# 03_SOC_PORT0_2.net
KiCad netlist of a schematic drawn in Altium Designer
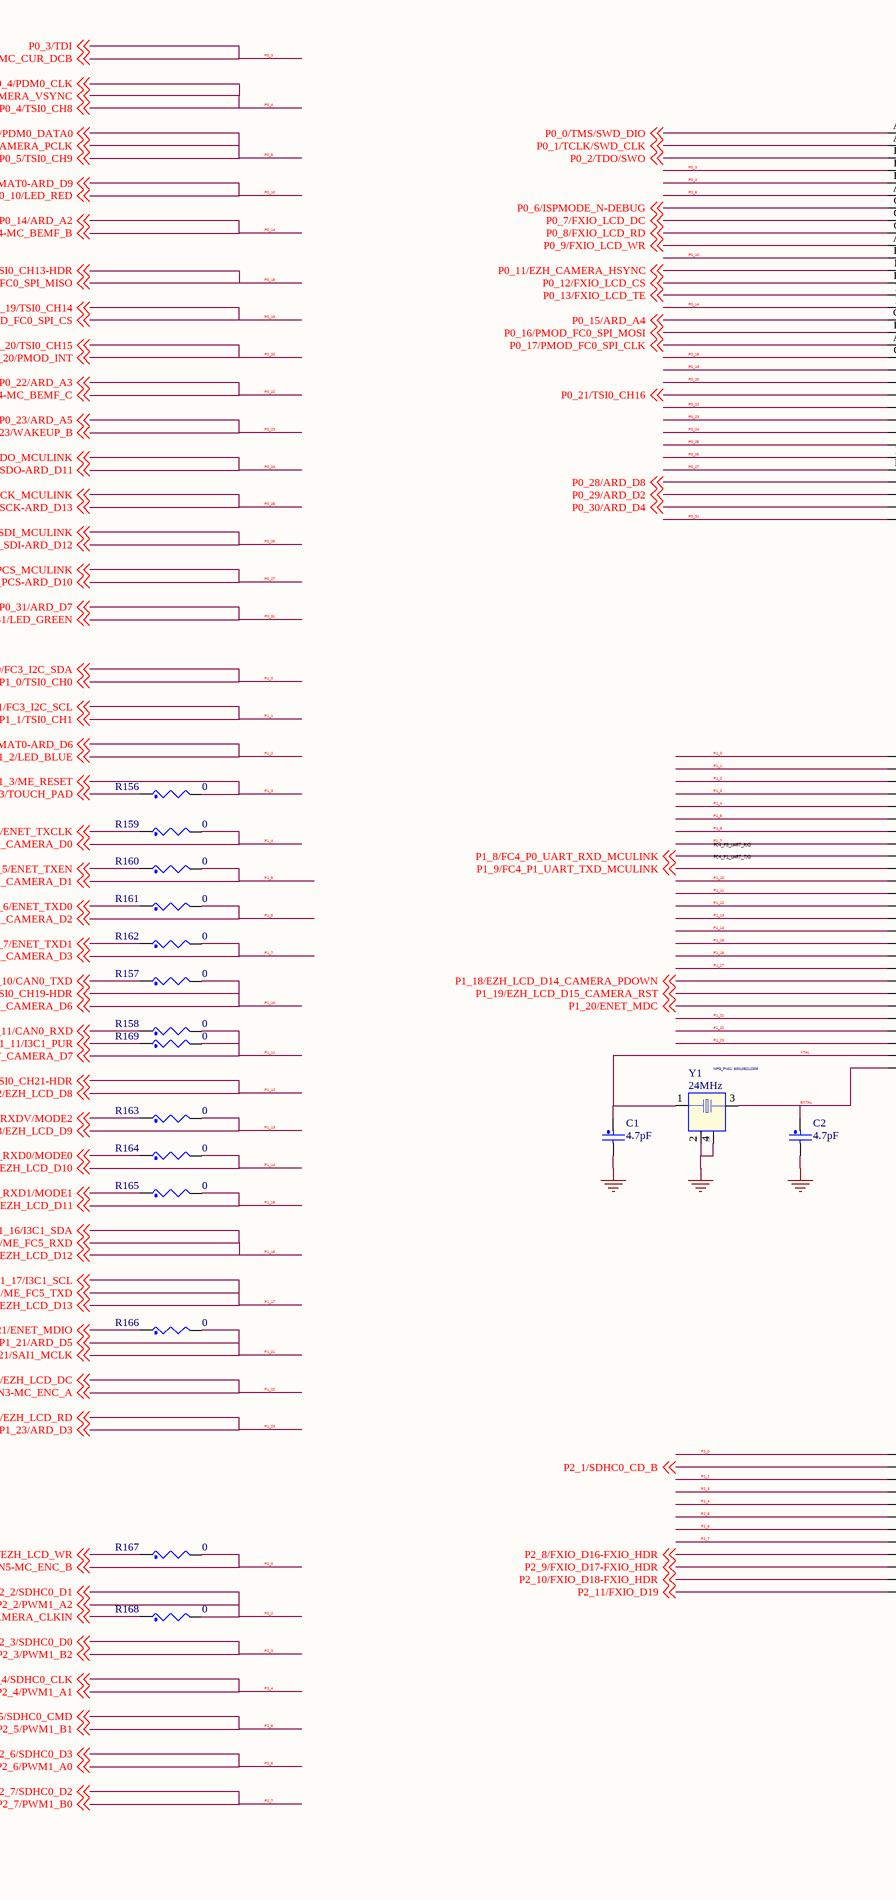
[diagram p0: 03 SOC_PORT0~2.SchDoc, left]
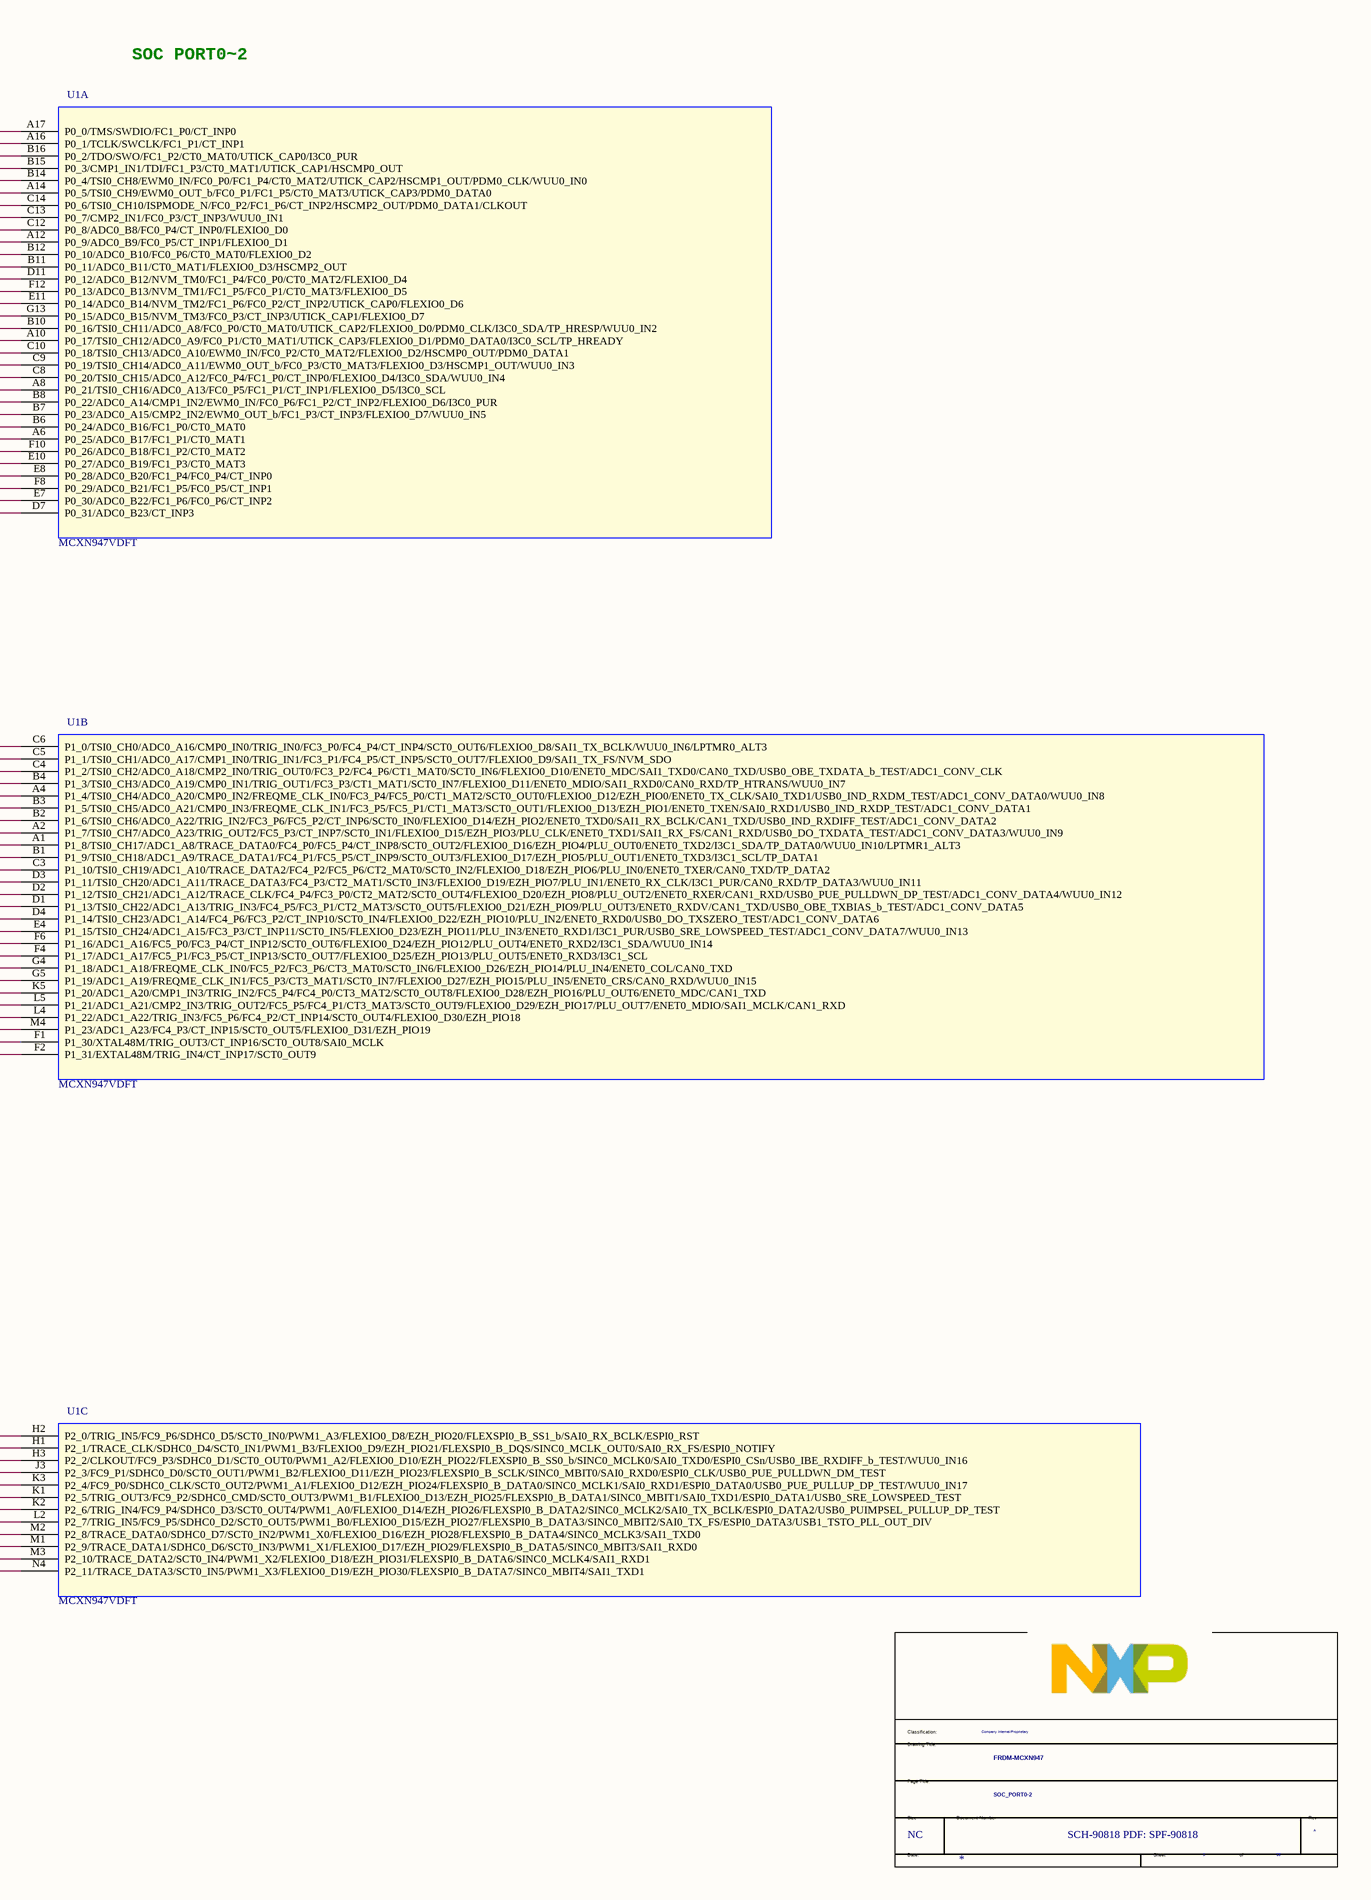
[diagram p1: 03 SOC_PORT0~2.SchDoc, right]

(export (version "E")
  (design (tool "Eeschema 10.0.6"))
  (components
    (comp (ref "C1")
      (value "4.7pF")
      (footprint "CC0402_25")
      (description "CAP CER 4.7PF 50V 0.5pF C0G 0402")
      (fields (field (name "TOLERANCE") "0.5pF"))
      (libsource (lib "*") (part "CAP_NP"))
    )
    (comp (ref "C2")
      (value "4.7pF")
      (footprint "CC0402_25")
      (description "CAP CER 4.7PF 50V 0.5pF C0G 0402")
      (fields (field (name "TOLERANCE") "0.5pF"))
      (libsource (lib "*") (part "CAP_NP"))
    )
    (comp (ref "R156")
      (value "0")
      (footprint "RC0603_OV")
      (description "RES MF ZERO OHM 1/10W -- 0603")
      (libsource (lib "*") (part "RES"))
    )
    (comp (ref "R157")
      (value "0")
      (footprint "RC0603_OV")
      (description "RES MF ZERO OHM 1/10W -- 0603")
      (libsource (lib "*") (part "RES"))
    )
    (comp (ref "R158")
      (value "0")
      (footprint "RC0603_OV")
      (description "RES MF ZERO OHM 1/10W -- 0603")
      (libsource (lib "*") (part "RES"))
    )
    (comp (ref "R159")
      (value "0")
      (footprint "RC0603_OV")
      (description "RES MF ZERO OHM 1/10W -- 0603")
      (libsource (lib "*") (part "RES"))
    )
    (comp (ref "R160")
      (value "0")
      (footprint "RC0603_OV")
      (description "RES MF ZERO OHM 1/10W -- 0603")
      (libsource (lib "*") (part "RES"))
    )
    (comp (ref "R161")
      (value "0")
      (footprint "RC0603_OV")
      (description "RES MF ZERO OHM 1/10W -- 0603")
      (libsource (lib "*") (part "RES"))
    )
    (comp (ref "R162")
      (value "0")
      (footprint "RC0603_OV")
      (description "RES MF ZERO OHM 1/10W -- 0603")
      (libsource (lib "*") (part "RES"))
    )
    (comp (ref "R163")
      (value "0")
      (footprint "RC0603_OV")
      (description "RES MF ZERO OHM 1/10W -- 0603")
      (libsource (lib "*") (part "RES"))
    )
    (comp (ref "R164")
      (value "0")
      (footprint "RC0603_OV")
      (description "RES MF ZERO OHM 1/10W -- 0603")
      (libsource (lib "*") (part "RES"))
    )
    (comp (ref "R165")
      (value "0")
      (footprint "RC0603_OV")
      (description "RES MF ZERO OHM 1/10W -- 0603")
      (libsource (lib "*") (part "RES"))
    )
    (comp (ref "R166")
      (value "0")
      (footprint "RC0603_OV")
      (description "RES MF ZERO OHM 1/10W -- 0603")
      (libsource (lib "*") (part "RES"))
    )
    (comp (ref "R167")
      (value "0")
      (footprint "RC0402_25")
      (description "RES MF ZERO OHM 1/16W 5% 0402")
      (fields (field (name "TOLERANCE") "5%"))
      (libsource (lib "*") (part "RES"))
    )
    (comp (ref "R168")
      (value "0")
      (footprint "RC0603_OV")
      (description "RES MF ZERO OHM 1/10W -- 0603")
      (libsource (lib "*") (part "RES"))
    )
    (comp (ref "R169")
      (value "0")
      (footprint "RC0402_25")
      (description "RES MF ZERO OHM 1/16W 5% 0402")
      (fields (field (name "TOLERANCE") "5%"))
      (libsource (lib "*") (part "RES"))
    )
    (comp (ref "U1")
      (value "MCXN947VDFT")
      (footprint "bga184_0p5_9x9_sm")
      (description "IC MCU LOW POWER 150MHz ARM Nirvana -- VFBGA184")
      (libsource (lib "*") (part "MCXN947VDFT_BGA_184P"))
    )
    (comp (ref "Y1")
      (value "24MHz")
      (footprint "xtal4_2p1x1p7mm_sm")
      (description "XTAL 24MHz 10ppm 8pF SMT")
      (fields (field (name "MFG_PN01") "830108212309"))
      (libsource (lib "*") (part "XTAL_4PIN"))
    )
  )
  (nets
    (net (code "1") (name "/EXTAL") (class "Default")
      (node (ref "C2") (pin "1") (pinfunction "1_1") (pintype "passive"))
      (node (ref "U1") (pin "F2") (pinfunction "P1_31/EXTAL48M/TRIG_IN4/CT_INP17/SCT0_OUT9_F2") (pintype "passive"))
      (node (ref "Y1") (pin "3") (pinfunction "3_3") (pintype "passive"))
    )
    (net (code "2") (name "/XTAL") (class "Default")
      (node (ref "C1") (pin "1") (pinfunction "1_1") (pintype "passive"))
      (node (ref "U1") (pin "F1") (pinfunction "P1_30/XTAL48M/TRIG_OUT3/CT_INP16/SCT0_OUT8/SAI0_MCLK_F1") (pintype "passive"))
      (node (ref "Y1") (pin "1") (pinfunction "1_1") (pintype "passive"))
    )
    (net (code "3") (name "GND") (class "Default")
      (node (ref "C1") (pin "2") (pinfunction "2_2") (pintype "passive"))
      (node (ref "C2") (pin "2") (pinfunction "2_2") (pintype "passive"))
      (node (ref "Y1") (pin "2") (pinfunction "GND1_2") (pintype "power_in"))
      (node (ref "Y1") (pin "4") (pinfunction "GND2_4") (pintype "power_in"))
    )
    (net (code "4") (name "P0_0{slash}TMS{slash}SWD_DIO") (class "Default")
      (node (ref "U1") (pin "A17") (pinfunction "P0_0/TMS/SWDIO/FC1_P0/CT_INP0_A17") (pintype "passive"))
    )
    (net (code "5") (name "P0_1{slash}TCLK{slash}SWD_CLK") (class "Default")
      (node (ref "U1") (pin "A16") (pinfunction "P0_1/TCLK/SWCLK/FC1_P1/CT_INP1_A16") (pintype "passive"))
    )
    (net (code "6") (name "P0_2{slash}TDO{slash}SWO") (class "Default")
      (node (ref "U1") (pin "B16") (pinfunction "P0_2/TDO/SWO/FC1_P2/CT0_MAT0/UTICK_CAP0/I3C0_PUR_B16") (pintype "passive"))
    )
    (net (code "7") (name "P0_3{slash}CMP1_IN1-MC_CUR_DCB") (class "Default")
      (node (ref "U1") (pin "B15") (pinfunction "P0_3/CMP1_IN1/TDI/FC1_P3/CT0_MAT1/UTICK_CAP1/HSCMP0_OUT_B15") (pintype "passive"))
    )
    (net (code "8") (name "P0_4{slash}EZH_CAMERA_VSYNC") (class "Default")
      (node (ref "U1") (pin "B14") (pinfunction "P0_4/TSI0_CH8/EWM0_IN/FC0_P0/FC1_P4/CT0_MAT2/UTICK_CAP2/HSCMP1_OUT/PDM0_CLK/WUU0_IN0_B14") (pintype "passive"))
    )
    (net (code "9") (name "P0_5{slash}EZH_CAMERA_PCLK") (class "Default")
      (node (ref "U1") (pin "A14") (pinfunction "P0_5/TSI0_CH9/EWM0_OUT_b/FC0_P1/FC1_P5/CT0_MAT3/UTICK_CAP3/PDM0_DATA0_A14") (pintype "passive"))
    )
    (net (code "10") (name "P0_6{slash}ISPMODE_N-DEBUG") (class "Default")
      (node (ref "U1") (pin "C14") (pinfunction "P0_6/TSI0_CH10/ISPMODE_N/FC0_P2/FC1_P6/CT_INP2/HSCMP2_OUT/PDM0_DATA1/CLKOUT_C14") (pintype "passive"))
    )
    (net (code "11") (name "P0_7{slash}FXIO_LCD_DC") (class "Default")
      (node (ref "U1") (pin "C13") (pinfunction "P0_7/CMP2_IN1/FC0_P3/CT_INP3/WUU0_IN1_C13") (pintype "passive"))
    )
    (net (code "12") (name "P0_8{slash}FXIO_LCD_RD") (class "Default")
      (node (ref "U1") (pin "C12") (pinfunction "P0_8/ADC0_B8/FC0_P4/CT_INP0/FLEXIO0_D0_C12") (pintype "passive"))
    )
    (net (code "13") (name "P0_9{slash}FXIO_LCD_WR") (class "Default")
      (node (ref "U1") (pin "A12") (pinfunction "P0_9/ADC0_B9/FC0_P5/CT_INP1/FLEXIO0_D1_A12") (pintype "passive"))
    )
    (net (code "14") (name "P0_10{slash}CT0_MAT0-ARD_D9") (class "Default")
      (node (ref "U1") (pin "B12") (pinfunction "P0_10/ADC0_B10/FC0_P6/CT0_MAT0/FLEXIO0_D2_B12") (pintype "passive"))
    )
    (net (code "15") (name "P0_11{slash}EZH_CAMERA_HSYNC") (class "Default")
      (node (ref "U1") (pin "B11") (pinfunction "P0_11/ADC0_B11/CT0_MAT1/FLEXIO0_D3/HSCMP2_OUT_B11") (pintype "passive"))
    )
    (net (code "16") (name "P0_12{slash}FXIO_LCD_CS") (class "Default")
      (node (ref "U1") (pin "D11") (pinfunction "P0_12/ADC0_B12/NVM_TM0/FC1_P4/FC0_P0/CT0_MAT2/FLEXIO0_D4_D11") (pintype "passive"))
    )
    (net (code "17") (name "P0_13{slash}FXIO_LCD_TE") (class "Default")
      (node (ref "U1") (pin "F12") (pinfunction "P0_13/ADC0_B13/NVM_TM1/FC1_P5/FC0_P1/CT0_MAT3/FLEXIO0_D5_F12") (pintype "passive"))
    )
    (net (code "18") (name "P0_14{slash}ADC0_B14-MC_BEMF_B") (class "Default")
      (node (ref "U1") (pin "E11") (pinfunction "P0_14/ADC0_B14/NVM_TM2/FC1_P6/FC0_P2/CT_INP2/UTICK_CAP0/FLEXIO0_D6_E11") (pintype "passive"))
    )
    (net (code "19") (name "P0_15{slash}ARD_A4") (class "Default")
      (node (ref "U1") (pin "G13") (pinfunction "P0_15/ADC0_B15/NVM_TM3/FC0_P3/CT_INP3/UTICK_CAP1/FLEXIO0_D7_G13") (pintype "passive"))
    )
    (net (code "20") (name "P0_16{slash}PMOD_FC0_SPI_MOSI") (class "Default")
      (node (ref "U1") (pin "B10") (pinfunction "P0_16/TSI0_CH11/ADC0_A8/FC0_P0/CT0_MAT0/UTICK_CAP2/FLEXIO0_D0/PDM0_CLK/I3C0_SDA/TP_HRESP/WUU0_IN2_B10") (pintype "passive"))
    )
    (net (code "21") (name "P0_17{slash}PMOD_FC0_SPI_CLK") (class "Default")
      (node (ref "U1") (pin "A10") (pinfunction "P0_17/TSI0_CH12/ADC0_A9/FC0_P1/CT0_MAT1/UTICK_CAP3/FLEXIO0_D1/PDM0_DATA0/I3C0_SCL/TP_HREADY_A10") (pintype "passive"))
    )
    (net (code "22") (name "P0_18{slash}PMOD_FC0_SPI_MISO") (class "Default")
      (node (ref "U1") (pin "C10") (pinfunction "P0_18/TSI0_CH13/ADC0_A10/EWM0_IN/FC0_P2/CT0_MAT2/FLEXIO0_D2/HSCMP0_OUT/PDM0_DATA1_C10") (pintype "passive"))
    )
    (net (code "23") (name "P0_19{slash}PMOD_FC0_SPI_CS") (class "Default")
      (node (ref "U1") (pin "C9") (pinfunction "P0_19/TSI0_CH14/ADC0_A11/EWM0_OUT_b/FC0_P3/CT0_MAT3/FLEXIO0_D3/HSCMP1_OUT/WUU0_IN3_C9") (pintype "passive"))
    )
    (net (code "24") (name "P0_20{slash}PMOD_INT") (class "Default")
      (node (ref "U1") (pin "C8") (pinfunction "P0_20/TSI0_CH15/ADC0_A12/FC0_P4/FC1_P0/CT_INP0/FLEXIO0_D4/I3C0_SDA/WUU0_IN4_C8") (pintype "passive"))
    )
    (net (code "25") (name "P0_21{slash}TSI0_CH16") (class "Default")
      (node (ref "U1") (pin "A8") (pinfunction "P0_21/TSI0_CH16/ADC0_A13/FC0_P5/FC1_P1/CT_INP1/FLEXIO0_D5/I3C0_SCL_A8") (pintype "passive"))
    )
    (net (code "26") (name "P0_22{slash}ADC0_A14-MC_BEMF_C") (class "Default")
      (node (ref "U1") (pin "B8") (pinfunction "P0_22/ADC0_A14/CMP1_IN2/EWM0_IN/FC0_P6/FC1_P2/CT_INP2/FLEXIO0_D6/I3C0_PUR_B8") (pintype "passive"))
    )
    (net (code "27") (name "P0_23{slash}ARD_A5") (class "Default")
      (node (ref "U1") (pin "B7") (pinfunction "P0_23/ADC0_A15/CMP2_IN2/EWM0_OUT_b/FC1_P3/CT_INP3/FLEXIO0_D7/WUU0_IN5_B7") (pintype "passive"))
    )
    (net (code "28") (name "P0_24{slash}FC1_SPI_SDO-ARD_D11") (class "Default")
      (node (ref "U1") (pin "B6") (pinfunction "P0_24/ADC0_B16/FC1_P0/CT0_MAT0_B6") (pintype "passive"))
    )
    (net (code "29") (name "P0_25{slash}FCI_SPI_SCK-ARD_D13") (class "Default")
      (node (ref "U1") (pin "A6") (pinfunction "P0_25/ADC0_B17/FC1_P1/CT0_MAT1_A6") (pintype "passive"))
    )
    (net (code "30") (name "P0_26{slash}FC1_SPI_SDI-ARD_D12") (class "Default")
      (node (ref "U1") (pin "F10") (pinfunction "P0_26/ADC0_B18/FC1_P2/CT0_MAT2_F10") (pintype "passive"))
    )
    (net (code "31") (name "P0_27{slash}FC1_SPI_PCS-ARD_D10") (class "Default")
      (node (ref "U1") (pin "E10") (pinfunction "P0_27/ADC0_B19/FC1_P3/CT0_MAT3_E10") (pintype "passive"))
    )
    (net (code "32") (name "P0_28{slash}ARD_D8") (class "Default")
      (node (ref "U1") (pin "E8") (pinfunction "P0_28/ADC0_B20/FC1_P4/FC0_P4/CT_INP0_E8") (pintype "passive"))
    )
    (net (code "33") (name "P0_29{slash}ARD_D2") (class "Default")
      (node (ref "U1") (pin "F8") (pinfunction "P0_29/ADC0_B21/FC1_P5/FC0_P5/CT_INP1_F8") (pintype "passive"))
    )
    (net (code "34") (name "P0_30{slash}ARD_D4") (class "Default")
      (node (ref "U1") (pin "E7") (pinfunction "P0_30/ADC0_B22/FC1_P6/FC0_P6/CT_INP2_E7") (pintype "passive"))
    )
    (net (code "35") (name "P0_31{slash}ARD_D7") (class "Default")
      (node (ref "U1") (pin "D7") (pinfunction "P0_31/ADC0_B23/CT_INP3_D7") (pintype "passive"))
    )
    (net (code "36") (name "P1_0{slash}FC3_I2C_SDA") (class "Default")
      (node (ref "U1") (pin "C6") (pinfunction "P1_0/TSI0_CH0/ADC0_A16/CMP0_IN0/TRIG_IN0/FC3_P0/FC4_P4/CT_INP4/SCT0_OUT6/FLEXIO0_D8/SAI1_TX_BCLK/WUU0_IN6/LPTMR0_ALT3_C6") (pintype "passive"))
    )
    (net (code "37") (name "P1_1{slash}FC3_I2C_SCL") (class "Default")
      (node (ref "U1") (pin "C5") (pinfunction "P1_1/TSI0_CH1/ADC0_A17/CMP1_IN0/TRIG_IN1/FC3_P1/FC4_P5/CT_INP5/SCT0_OUT7/FLEXIO0_D9/SAI1_TX_FS/NVM_SDO_C5") (pintype "passive"))
    )
    (net (code "38") (name "P1_2{slash}CT1_MAT0-ARD_D6") (class "Default")
      (node (ref "U1") (pin "C4") (pinfunction "P1_2/TSI0_CH2/ADC0_A18/CMP2_IN0/TRIG_OUT0/FC3_P2/FC4_P6/CT1_MAT0/SCT0_IN6/FLEXIO0_D10/ENET0_MDC/SAI1_TXD0/CAN0_TXD/USB0_OBE_TXDATA_b_TEST/ADC1_CONV_CLK_C4") (pintype "passive"))
    )
    (net (code "39") (name "P1_3{slash}ME_RESET") (class "Default")
      (node (ref "R156") (pin "2") (pinfunction "2_2") (pintype "passive"))
      (node (ref "U1") (pin "B4") (pinfunction "P1_3/TSI0_CH3/ADC0_A19/CMP0_IN1/TRIG_OUT1/FC3_P3/CT1_MAT1/SCT0_IN7/FLEXIO0_D11/ENET0_MDIO/SAI1_RXD0/CAN0_RXD/TP_HTRANS/WUU0_IN7_B4") (pintype "passive"))
    )
    (net (code "40") (name "P1_3{slash}TOUCH_PAD") (class "Default")
      (node (ref "R156") (pin "1") (pinfunction "1_1") (pintype "passive"))
    )
    (net (code "41") (name "P1_4{slash}ENET_TXCLK") (class "Default")
      (node (ref "R159") (pin "1") (pinfunction "1_1") (pintype "passive"))
    )
    (net (code "42") (name "P1_4{slash}EZH_LCD_D0_CAMERA_D0") (class "Default")
      (node (ref "R159") (pin "2") (pinfunction "2_2") (pintype "passive"))
      (node (ref "U1") (pin "A4") (pinfunction "P1_4/TSI0_CH4/ADC0_A20/CMP0_IN2/FREQME_CLK_IN0/FC3_P4/FC5_P0/CT1_MAT2/SCT0_OUT0/FLEXIO0_D12/EZH_PIO0/ENET0_TX_CLK/SAI0_TXD1/USB0_IND_RXDM_TEST/ADC1_CONV_DATA0/WUU0_IN8_A4") (pintype "passive"))
    )
    (net (code "43") (name "P1_5{slash}ENET_TXEN") (class "Default")
      (node (ref "R160") (pin "1") (pinfunction "1_1") (pintype "passive"))
    )
    (net (code "44") (name "P1_5{slash}EZH_LCD_D1_CAMERA_D1") (class "Default")
      (node (ref "R160") (pin "2") (pinfunction "2_2") (pintype "passive"))
      (node (ref "U1") (pin "B3") (pinfunction "P1_5/TSI0_CH5/ADC0_A21/CMP0_IN3/FREQME_CLK_IN1/FC3_P5/FC5_P1/CT1_MAT3/SCT0_OUT1/FLEXIO0_D13/EZH_PIO1/ENET0_TXEN/SAI0_RXD1/USB0_IND_RXDP_TEST/ADC1_CONV_DATA1_B3") (pintype "passive"))
    )
    (net (code "45") (name "P1_6{slash}ENET_TXD0") (class "Default")
      (node (ref "R161") (pin "1") (pinfunction "1_1") (pintype "passive"))
    )
    (net (code "46") (name "P1_6{slash}EZH_LCD_D2_CAMERA_D2") (class "Default")
      (node (ref "R161") (pin "2") (pinfunction "2_2") (pintype "passive"))
      (node (ref "U1") (pin "B2") (pinfunction "P1_6/TSI0_CH6/ADC0_A22/TRIG_IN2/FC3_P6/FC5_P2/CT_INP6/SCT0_IN0/FLEXIO0_D14/EZH_PIO2/ENET0_TXD0/SAI1_RX_BCLK/CAN1_TXD/USB0_IND_RXDIFF_TEST/ADC1_CONV_DATA2_B2") (pintype "passive"))
    )
    (net (code "47") (name "P1_7{slash}ENET_TXD1") (class "Default")
      (node (ref "R162") (pin "1") (pinfunction "1_1") (pintype "passive"))
    )
    (net (code "48") (name "P1_7{slash}EZH_LCD_D3_CAMERA_D3") (class "Default")
      (node (ref "R162") (pin "2") (pinfunction "2_2") (pintype "passive"))
      (node (ref "U1") (pin "A2") (pinfunction "P1_7/TSI0_CH7/ADC0_A23/TRIG_OUT2/FC5_P3/CT_INP7/SCT0_IN1/FLEXIO0_D15/EZH_PIO3/PLU_CLK/ENET0_TXD1/SAI1_RX_FS/CAN1_RXD/USB0_DO_TXDATA_TEST/ADC1_CONV_DATA3/WUU0_IN9_A2") (pintype "passive"))
    )
    (net (code "49") (name "P1_8{slash}FC4_P0_UART_RXD_MCULINK") (class "Default")
      (node (ref "U1") (pin "A1") (pinfunction "P1_8/TSI0_CH17/ADC1_A8/TRACE_DATA0/FC4_P0/FC5_P4/CT_INP8/SCT0_OUT2/FLEXIO0_D16/EZH_PIO4/PLU_OUT0/ENET0_TXD2/I3C1_SDA/TP_DATA0/WUU0_IN10/LPTMR1_ALT3_A1") (pintype "passive"))
    )
    (net (code "50") (name "P1_9{slash}FC4_P1_UART_TXD_MCULINK") (class "Default")
      (node (ref "U1") (pin "B1") (pinfunction "P1_9/TSI0_CH18/ADC1_A9/TRACE_DATA1/FC4_P1/FC5_P5/CT_INP9/SCT0_OUT3/FLEXIO0_D17/EZH_PIO5/PLU_OUT1/ENET0_TXD3/I3C1_SCL/TP_DATA1_B1") (pintype "passive"))
    )
    (net (code "51") (name "P1_10{slash}CAN0_TXD") (class "Default")
      (node (ref "R157") (pin "1") (pinfunction "1_1") (pintype "passive"))
    )
    (net (code "52") (name "P1_10{slash}EZH_LCD_D6_CAMERA_D6") (class "Default")
      (node (ref "R157") (pin "2") (pinfunction "2_2") (pintype "passive"))
      (node (ref "U1") (pin "C3") (pinfunction "P1_10/TSI0_CH19/ADC1_A10/TRACE_DATA2/FC4_P2/FC5_P6/CT2_MAT0/SCT0_IN2/FLEXIO0_D18/EZH_PIO6/PLU_IN0/ENET0_TXER/CAN0_TXD/TP_DATA2_C3") (pintype "passive"))
    )
    (net (code "53") (name "P1_11{slash}CAN0_RXD") (class "Default")
      (node (ref "R158") (pin "1") (pinfunction "1_1") (pintype "passive"))
    )
    (net (code "54") (name "P1_11{slash}EZH_LCD_D7_CAMERA_D7") (class "Default")
      (node (ref "R158") (pin "2") (pinfunction "2_2") (pintype "passive"))
      (node (ref "R169") (pin "2") (pinfunction "2_2") (pintype "passive"))
      (node (ref "U1") (pin "D3") (pinfunction "P1_11/TSI0_CH20/ADC1_A11/TRACE_DATA3/FC4_P3/CT2_MAT1/SCT0_IN3/FLEXIO0_D19/EZH_PIO7/PLU_IN1/ENET0_RX_CLK/I3C1_PUR/CAN0_RXD/TP_DATA3/WUU0_IN11_D3") (pintype "passive"))
    )
    (net (code "55") (name "P1_11{slash}I3C1_PUR") (class "Default")
      (node (ref "R169") (pin "1") (pinfunction "1_1") (pintype "passive"))
    )
    (net (code "56") (name "P1_12{slash}EZH_LCD_D8") (class "Default")
      (node (ref "U1") (pin "D2") (pinfunction "P1_12/TSI0_CH21/ADC1_A12/TRACE_CLK/FC4_P4/FC3_P0/CT2_MAT2/SCT0_OUT4/FLEXIO0_D20/EZH_PIO8/PLU_OUT2/ENET0_RXER/CAN1_RXD/USB0_PUE_PULLDWN_DP_TEST/ADC1_CONV_DATA4/WUU0_IN12_D2") (pintype "passive"))
    )
    (net (code "57") (name "P1_13{slash}ENET_RXDV{slash}MODE2") (class "Default")
      (node (ref "R163") (pin "1") (pinfunction "1_1") (pintype "passive"))
    )
    (net (code "58") (name "P1_13{slash}EZH_LCD_D9") (class "Default")
      (node (ref "R163") (pin "2") (pinfunction "2_2") (pintype "passive"))
      (node (ref "U1") (pin "D1") (pinfunction "P1_13/TSI0_CH22/ADC1_A13/TRIG_IN3/FC4_P5/FC3_P1/CT2_MAT3/SCT0_OUT5/FLEXIO0_D21/EZH_PIO9/PLU_OUT3/ENET0_RXDV/CAN1_TXD/USB0_OBE_TXBIAS_b_TEST/ADC1_CONV_DATA5_D1") (pintype "passive"))
    )
    (net (code "59") (name "P1_14{slash}ENET_RXD0{slash}MODE0") (class "Default")
      (node (ref "R164") (pin "1") (pinfunction "1_1") (pintype "passive"))
    )
    (net (code "60") (name "P1_14{slash}EZH_LCD_D10") (class "Default")
      (node (ref "R164") (pin "2") (pinfunction "2_2") (pintype "passive"))
      (node (ref "U1") (pin "D4") (pinfunction "P1_14/TSI0_CH23/ADC1_A14/FC4_P6/FC3_P2/CT_INP10/SCT0_IN4/FLEXIO0_D22/EZH_PIO10/PLU_IN2/ENET0_RXD0/USB0_DO_TXSZERO_TEST/ADC1_CONV_DATA6_D4") (pintype "passive"))
    )
    (net (code "61") (name "P1_15{slash}ENET_RXD1{slash}MODE1") (class "Default")
      (node (ref "R165") (pin "1") (pinfunction "1_1") (pintype "passive"))
    )
    (net (code "62") (name "P1_15{slash}EZH_LCD_D11") (class "Default")
      (node (ref "R165") (pin "2") (pinfunction "2_2") (pintype "passive"))
      (node (ref "U1") (pin "E4") (pinfunction "P1_15/TSI0_CH24/ADC1_A15/FC3_P3/CT_INP11/SCT0_IN5/FLEXIO0_D23/EZH_PIO11/PLU_IN3/ENET0_RXD1/I3C1_PUR/USB0_SRE_LOWSPEED_TEST/ADC1_CONV_DATA7/WUU0_IN13_E4") (pintype "passive"))
    )
    (net (code "63") (name "P1_16{slash}EZH_LCD_D12") (class "Default")
      (node (ref "U1") (pin "F6") (pinfunction "P1_16/ADC1_A16/FC5_P0/FC3_P4/CT_INP12/SCT0_OUT6/FLEXIO0_D24/EZH_PIO12/PLU_OUT4/ENET0_RXD2/I3C1_SDA/WUU0_IN14_F6") (pintype "passive"))
    )
    (net (code "64") (name "P1_17{slash}EZH_LCD_D13") (class "Default")
      (node (ref "U1") (pin "F4") (pinfunction "P1_17/ADC1_A17/FC5_P1/FC3_P5/CT_INP13/SCT0_OUT7/FLEXIO0_D25/EZH_PIO13/PLU_OUT5/ENET0_RXD3/I3C1_SCL_F4") (pintype "passive"))
    )
    (net (code "65") (name "P1_18{slash}EZH_LCD_D14_CAMERA_PDOWN") (class "Default")
      (node (ref "U1") (pin "G4") (pinfunction "P1_18/ADC1_A18/FREQME_CLK_IN0/FC5_P2/FC3_P6/CT3_MAT0/SCT0_IN6/FLEXIO0_D26/EZH_PIO14/PLU_IN4/ENET0_COL/CAN0_TXD_G4") (pintype "passive"))
    )
    (net (code "66") (name "P1_19{slash}EZH_LCD_D15_CAMERA_RST") (class "Default")
      (node (ref "U1") (pin "G5") (pinfunction "P1_19/ADC1_A19/FREQME_CLK_IN1/FC5_P3/CT3_MAT1/SCT0_IN7/FLEXIO0_D27/EZH_PIO15/PLU_IN5/ENET0_CRS/CAN0_RXD/WUU0_IN15_G5") (pintype "passive"))
    )
    (net (code "67") (name "P1_20{slash}ENET_MDC") (class "Default")
      (node (ref "U1") (pin "K5") (pinfunction "P1_20/ADC1_A20/CMP1_IN3/TRIG_IN2/FC5_P4/FC4_P0/CT3_MAT2/SCT0_OUT8/FLEXIO0_D28/EZH_PIO16/PLU_OUT6/ENET0_MDC/CAN1_TXD_K5") (pintype "passive"))
    )
    (net (code "68") (name "P1_21{slash}ARD_D5") (class "Default")
      (node (ref "R166") (pin "2") (pinfunction "2_2") (pintype "passive"))
      (node (ref "U1") (pin "L5") (pinfunction "P1_21/ADC1_A21/CMP2_IN3/TRIG_OUT2/FC5_P5/FC4_P1/CT3_MAT3/SCT0_OUT9/FLEXIO0_D29/EZH_PIO17/PLU_OUT7/ENET0_MDIO/SAI1_MCLK/CAN1_RXD_L5") (pintype "passive"))
    )
    (net (code "69") (name "P1_21{slash}ENET_MDIO") (class "Default")
      (node (ref "R166") (pin "1") (pinfunction "1_1") (pintype "passive"))
    )
    (net (code "70") (name "P1_22{slash}EZH_LCD_DC") (class "Default")
      (node (ref "U1") (pin "L4") (pinfunction "P1_22/ADC1_A22/TRIG_IN3/FC5_P6/FC4_P2/CT_INP14/SCT0_OUT4/FLEXIO0_D30/EZH_PIO18_L4") (pintype "passive"))
    )
    (net (code "71") (name "P1_23{slash}ARD_D3") (class "Default")
      (node (ref "U1") (pin "M4") (pinfunction "P1_23/ADC1_A23/FC4_P3/CT_INP15/SCT0_OUT5/FLEXIO0_D31/EZH_PIO19_M4") (pintype "passive"))
    )
    (net (code "72") (name "P2_0{slash}EZH_LCD_WR") (class "Default")
      (node (ref "R167") (pin "1") (pinfunction "1_1") (pintype "passive"))
    )
    (net (code "73") (name "P2_0{slash}TRIG_IN5-MC_ENC_B") (class "Default")
      (node (ref "R167") (pin "2") (pinfunction "2_2") (pintype "passive"))
      (node (ref "U1") (pin "H2") (pinfunction "P2_0/TRIG_IN5/FC9_P6/SDHC0_D5/SCT0_IN0/PWM1_A3/FLEXIO0_D8/EZH_PIO20/FLEXSPI0_B_SS1_b/SAI0_RX_BCLK/ESPI0_RST_H2") (pintype "passive"))
    )
    (net (code "74") (name "P2_1{slash}SDHC0_CD_B") (class "Default")
      (node (ref "U1") (pin "H1") (pinfunction "P2_1/TRACE_CLK/SDHC0_D4/SCT0_IN1/PWM1_B3/FLEXIO0_D9/EZH_PIO21/FLEXSPI0_B_DQS/SINC0_MCLK_OUT0/SAI0_RX_FS/ESPI0_NOTIFY_H1") (pintype "passive"))
    )
    (net (code "75") (name "P2_2{slash}CAMERA_CLKIN") (class "Default")
      (node (ref "R168") (pin "1") (pinfunction "1_1") (pintype "passive"))
    )
    (net (code "76") (name "P2_2{slash}PWM1_A2") (class "Default")
      (node (ref "R168") (pin "2") (pinfunction "2_2") (pintype "passive"))
      (node (ref "U1") (pin "H3") (pinfunction "P2_2/CLKOUT/FC9_P3/SDHC0_D1/SCT0_OUT0/PWM1_A2/FLEXIO0_D10/EZH_PIO22/FLEXSPI0_B_SS0_b/SINC0_MCLK0/SAI0_TXD0/ESPI0_CSn/USB0_IBE_RXDIFF_b_TEST/WUU0_IN16_H3") (pintype "passive"))
    )
    (net (code "77") (name "P2_3{slash}PWM1_B2") (class "Default")
      (node (ref "U1") (pin "J3") (pinfunction "P2_3/FC9_P1/SDHC0_D0/SCT0_OUT1/PWM1_B2/FLEXIO0_D11/EZH_PIO23/FLEXSPI0_B_SCLK/SINC0_MBIT0/SAI0_RXD0/ESPI0_CLK/USB0_PUE_PULLDWN_DM_TEST_J3") (pintype "passive"))
    )
    (net (code "78") (name "P2_4{slash}PWM1_A1") (class "Default")
      (node (ref "U1") (pin "K3") (pinfunction "P2_4/FC9_P0/SDHC0_CLK/SCT0_OUT2/PWM1_A1/FLEXIO0_D12/EZH_PIO24/FLEXSPI0_B_DATA0/SINC0_MCLK1/SAI0_RXD1/ESPI0_DATA0/USB0_PUE_PULLUP_DP_TEST/WUU0_IN17_K3") (pintype "passive"))
    )
    (net (code "79") (name "P2_5{slash}PWM1_B1") (class "Default")
      (node (ref "U1") (pin "K1") (pinfunction "P2_5/TRIG_OUT3/FC9_P2/SDHC0_CMD/SCT0_OUT3/PWM1_B1/FLEXIO0_D13/EZH_PIO25/FLEXSPI0_B_DATA1/SINC0_MBIT1/SAI0_TXD1/ESPI0_DATA1/USB0_SRE_LOWSPEED_TEST_K1") (pintype "passive"))
    )
    (net (code "80") (name "P2_6{slash}PWM1_A0") (class "Default")
      (node (ref "U1") (pin "K2") (pinfunction "P2_6/TRIG_IN4/FC9_P4/SDHC0_D3/SCT0_OUT4/PWM1_A0/FLEXIO0_D14/EZH_PIO26/FLEXSPI0_B_DATA2/SINC0_MCLK2/SAI0_TX_BCLK/ESPI0_DATA2/USB0_PUIMPSEL_PULLUP_DP_TEST_K2") (pintype "passive"))
    )
    (net (code "81") (name "P2_7{slash}PWM1_B0") (class "Default")
      (node (ref "U1") (pin "L2") (pinfunction "P2_7/TRIG_IN5/FC9_P5/SDHC0_D2/SCT0_OUT5/PWM1_B0/FLEXIO0_D15/EZH_PIO27/FLEXSPI0_B_DATA3/SINC0_MBIT2/SAI0_TX_FS/ESPI0_DATA3/USB1_TSTO_PLL_OUT_DIV_L2") (pintype "passive"))
    )
    (net (code "82") (name "P2_8{slash}FXIO_D16-FXIO_HDR") (class "Default")
      (node (ref "U1") (pin "M2") (pinfunction "P2_8/TRACE_DATA0/SDHC0_D7/SCT0_IN2/PWM1_X0/FLEXIO0_D16/EZH_PIO28/FLEXSPI0_B_DATA4/SINC0_MCLK3/SAI1_TXD0_M2") (pintype "passive"))
    )
    (net (code "83") (name "P2_9{slash}FXIO_D17-FXIO_HDR") (class "Default")
      (node (ref "U1") (pin "M1") (pinfunction "P2_9/TRACE_DATA1/SDHC0_D6/SCT0_IN3/PWM1_X1/FLEXIO0_D17/EZH_PIO29/FLEXSPI0_B_DATA5/SINC0_MBIT3/SAI1_RXD0_M1") (pintype "passive"))
    )
    (net (code "84") (name "P2_10{slash}FXIO_D18-FXIO_HDR") (class "Default")
      (node (ref "U1") (pin "M3") (pinfunction "P2_10/TRACE_DATA2/SCT0_IN4/PWM1_X2/FLEXIO0_D18/EZH_PIO31/FLEXSPI0_B_DATA6/SINC0_MCLK4/SAI1_RXD1_M3") (pintype "passive"))
    )
    (net (code "85") (name "P2_11{slash}FXIO_D19") (class "Default")
      (node (ref "U1") (pin "N4") (pinfunction "P2_11/TRACE_DATA3/SCT0_IN5/PWM1_X3/FLEXIO0_D19/EZH_PIO30/FLEXSPI0_B_DATA7/SINC0_MBIT4/SAI1_TXD1_N4") (pintype "passive"))
    )
  )
)
